# D1MBLUE.net
KiCad netlist of a schematic drawn in EAGLE
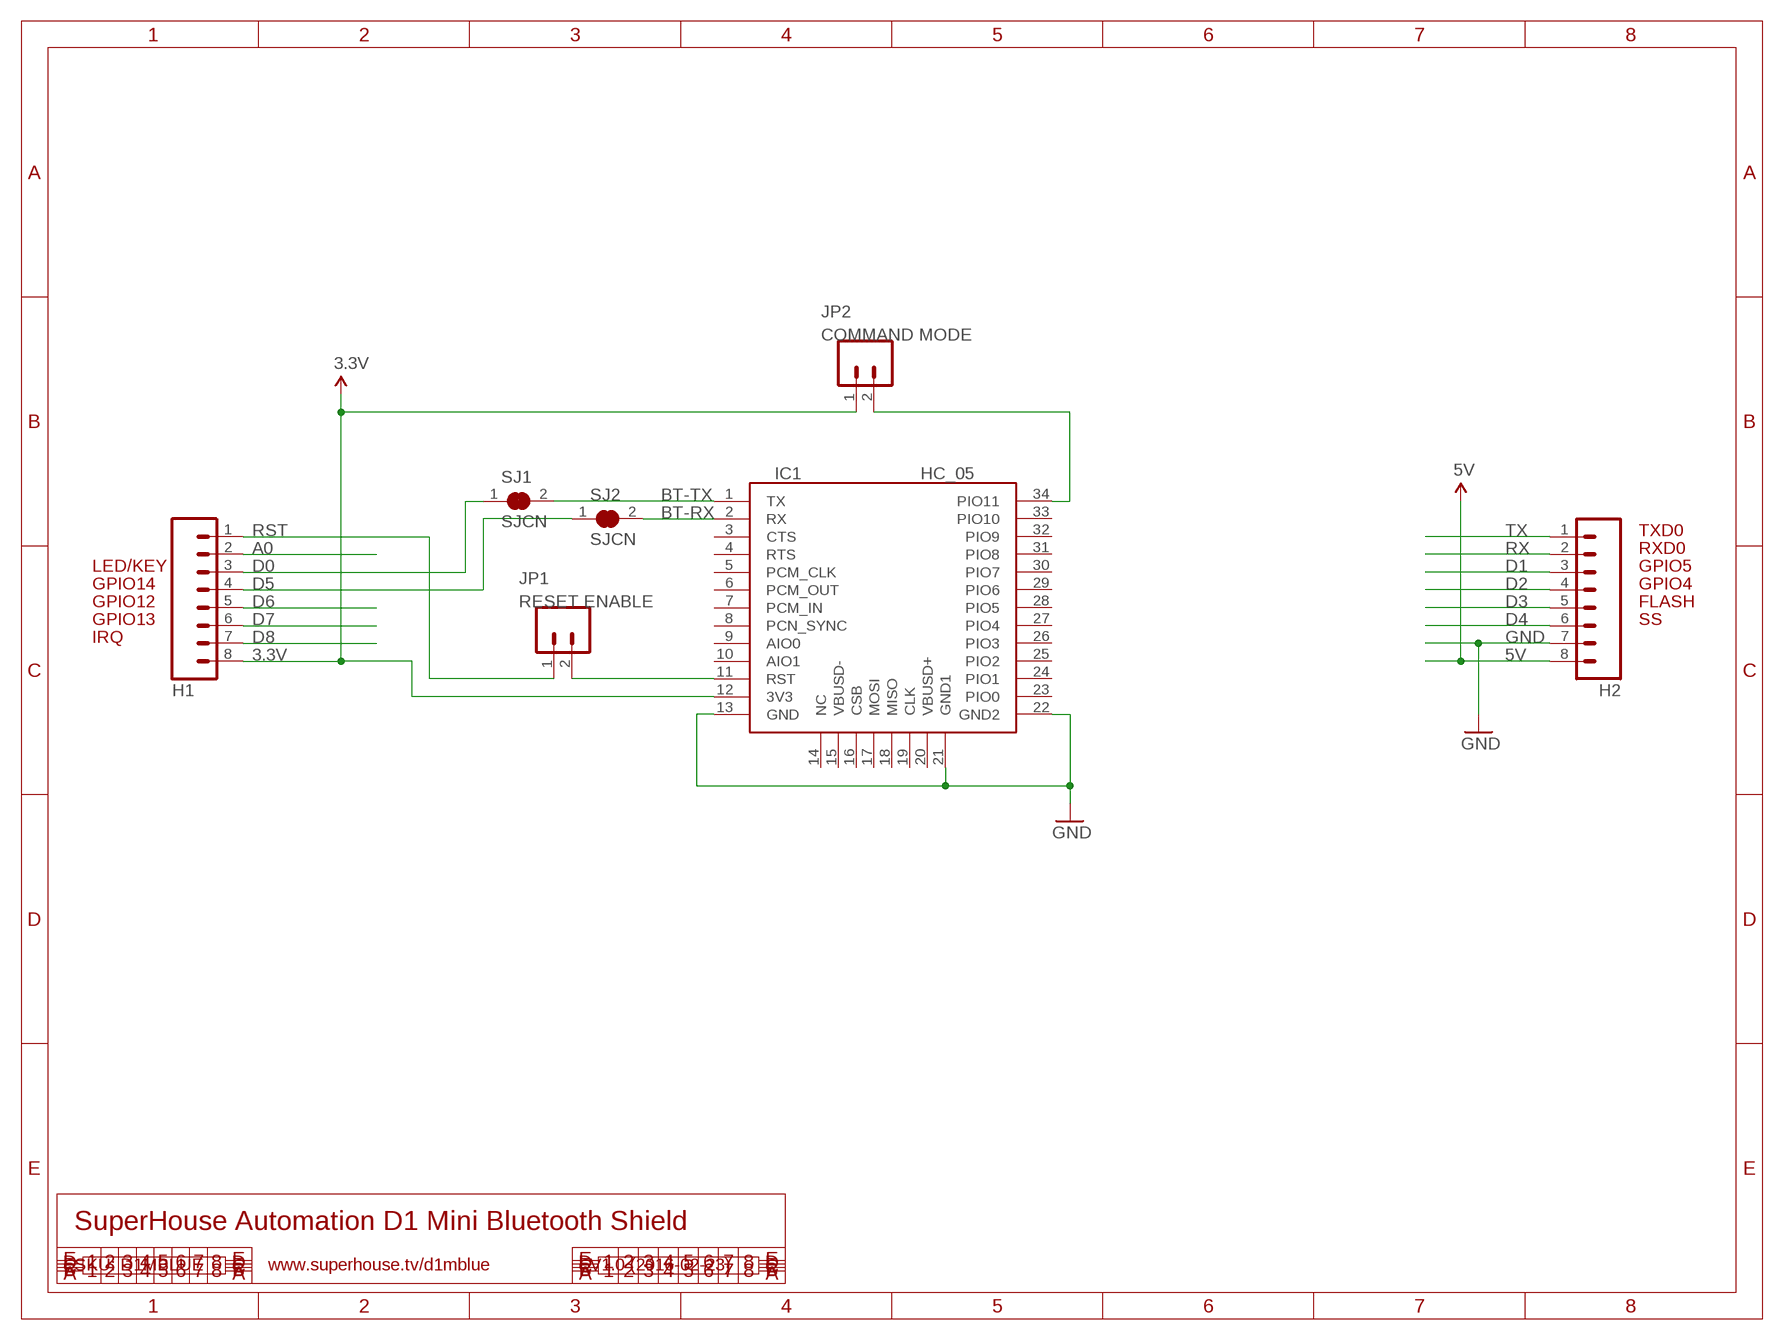
[diagram p0: schematic, sheet 1]

(export (version "E")
  (design (tool "Eeschema 10.0.6"))
  (components
    (comp (ref "H1")
      (value "M08")
      (footprint "eagle-import:1X08")
      (libsource (lib "eagle-import") (part "M08"))
    )
    (comp (ref "H2")
      (value "M08")
      (footprint "eagle-import:1X08")
      (libsource (lib "eagle-import") (part "M08"))
    )
    (comp (ref "IC1")
      (value "HC_05")
      (footprint "eagle-import:BLUETOOTH_SMD")
      (libsource (lib "eagle-import") (part "HC_05"))
    )
    (comp (ref "JP1")
      (value "RESET ENABLE")
      (footprint "eagle-import:1X02")
      (libsource (lib "eagle-import") (part "M02PTH"))
    )
    (comp (ref "JP2")
      (value "COMMAND MODE")
      (footprint "eagle-import:1X02")
      (libsource (lib "eagle-import") (part "M02PTH"))
    )
    (comp (ref "SJ1")
      (value "SJCN")
      (footprint "eagle-import:SJC")
      (libsource (lib "eagle-import") (part "SJCN"))
    )
    (comp (ref "SJ2")
      (value "SJCN")
      (footprint "eagle-import:SJC")
      (libsource (lib "eagle-import") (part "SJCN"))
    )
  )
  (nets
    (net (code "1") (name "/A0") (class "Default")
      (node (ref "H1") (pin "2") (pinfunction "2_2") (pintype "passive"))
    )
    (net (code "2") (name "/BT-RX") (class "Default")
      (node (ref "IC1") (pin "2") (pinfunction "RX_2") (pintype "bidirectional"))
      (node (ref "SJ2") (pin "2") (pinfunction "2_2") (pintype "passive"))
    )
    (net (code "3") (name "/BT-TX") (class "Default")
      (node (ref "IC1") (pin "1") (pinfunction "TX_1") (pintype "bidirectional"))
      (node (ref "SJ1") (pin "2") (pinfunction "2_2") (pintype "passive"))
    )
    (net (code "4") (name "/D0") (class "Default")
      (node (ref "H1") (pin "3") (pinfunction "3_3") (pintype "passive"))
      (node (ref "SJ1") (pin "1") (pinfunction "1_1") (pintype "passive"))
    )
    (net (code "5") (name "/D1") (class "Default")
      (node (ref "H2") (pin "3") (pinfunction "3_3") (pintype "passive"))
    )
    (net (code "6") (name "/D2") (class "Default")
      (node (ref "H2") (pin "4") (pinfunction "4_4") (pintype "passive"))
    )
    (net (code "7") (name "/D3") (class "Default")
      (node (ref "H2") (pin "5") (pinfunction "5_5") (pintype "passive"))
    )
    (net (code "8") (name "/D4") (class "Default")
      (node (ref "H2") (pin "6") (pinfunction "6_6") (pintype "passive"))
    )
    (net (code "9") (name "/D5") (class "Default")
      (node (ref "H1") (pin "4") (pinfunction "4_4") (pintype "passive"))
      (node (ref "SJ2") (pin "1") (pinfunction "1_1") (pintype "passive"))
    )
    (net (code "10") (name "/D6") (class "Default")
      (node (ref "H1") (pin "5") (pinfunction "5_5") (pintype "passive"))
    )
    (net (code "11") (name "/D7") (class "Default")
      (node (ref "H1") (pin "6") (pinfunction "6_6") (pintype "passive"))
    )
    (net (code "12") (name "/D8") (class "Default")
      (node (ref "H1") (pin "7") (pinfunction "7_7") (pintype "passive"))
    )
    (net (code "13") (name "/RST") (class "Default")
      (node (ref "H1") (pin "1") (pinfunction "1_1") (pintype "passive"))
      (node (ref "JP1") (pin "1") (pinfunction "1_1") (pintype "passive"))
    )
    (net (code "14") (name "/RX") (class "Default")
      (node (ref "H2") (pin "2") (pinfunction "2_2") (pintype "passive"))
    )
    (net (code "15") (name "/TX") (class "Default")
      (node (ref "H2") (pin "1") (pinfunction "1_1") (pintype "passive"))
    )
    (net (code "16") (name "3.3V") (class "Default")
      (node (ref "H1") (pin "8") (pinfunction "8_8") (pintype "passive"))
      (node (ref "IC1") (pin "12") (pinfunction "3V3_12") (pintype "bidirectional"))
      (node (ref "JP2") (pin "1") (pinfunction "1_1") (pintype "passive"))
    )
    (net (code "17") (name "5V") (class "Default")
      (node (ref "H2") (pin "8") (pinfunction "8_8") (pintype "passive"))
    )
    (net (code "18") (name "GND") (class "Default")
      (node (ref "H2") (pin "7") (pinfunction "7_7") (pintype "passive"))
      (node (ref "IC1") (pin "13") (pinfunction "GND_13") (pintype "bidirectional"))
      (node (ref "IC1") (pin "21") (pinfunction "GND1_21") (pintype "bidirectional"))
      (node (ref "IC1") (pin "22") (pinfunction "GND2_22") (pintype "bidirectional"))
    )
    (net (code "19") (name "Net-(IC1-PIO11)") (class "Default")
      (node (ref "IC1") (pin "34") (pinfunction "PIO11_34") (pintype "bidirectional"))
      (node (ref "JP2") (pin "2") (pinfunction "2_2") (pintype "passive"))
    )
    (net (code "20") (name "Net-(IC1-RST)") (class "Default")
      (node (ref "IC1") (pin "11") (pinfunction "RST_11") (pintype "bidirectional"))
      (node (ref "JP1") (pin "2") (pinfunction "2_2") (pintype "passive"))
    )
    (net (code "21") (name "unconnected-(IC1-AIO0-Pad9)") (class "Default")
      (node (ref "IC1") (pin "9") (pinfunction "AIO0_9") (pintype "bidirectional"))
    )
    (net (code "22") (name "unconnected-(IC1-AIO1-Pad10)") (class "Default")
      (node (ref "IC1") (pin "10") (pinfunction "AIO1_10") (pintype "bidirectional"))
    )
    (net (code "23") (name "unconnected-(IC1-CLK-Pad19)") (class "Default")
      (node (ref "IC1") (pin "19") (pinfunction "CLK_19") (pintype "bidirectional"))
    )
    (net (code "24") (name "unconnected-(IC1-CSB-Pad16)") (class "Default")
      (node (ref "IC1") (pin "16") (pinfunction "CSB_16") (pintype "bidirectional"))
    )
    (net (code "25") (name "unconnected-(IC1-CTS-Pad3)") (class "Default")
      (node (ref "IC1") (pin "3") (pinfunction "CTS_3") (pintype "bidirectional"))
    )
    (net (code "26") (name "unconnected-(IC1-MISO-Pad18)") (class "Default")
      (node (ref "IC1") (pin "18") (pinfunction "MISO_18") (pintype "bidirectional"))
    )
    (net (code "27") (name "unconnected-(IC1-MOSI-Pad17)") (class "Default")
      (node (ref "IC1") (pin "17") (pinfunction "MOSI_17") (pintype "bidirectional"))
    )
    (net (code "28") (name "unconnected-(IC1-NC-Pad14)") (class "Default")
      (node (ref "IC1") (pin "14") (pinfunction "NC_14") (pintype "bidirectional"))
    )
    (net (code "29") (name "unconnected-(IC1-PCM_CLK-Pad5)") (class "Default")
      (node (ref "IC1") (pin "5") (pinfunction "PCM_CLK_5") (pintype "bidirectional"))
    )
    (net (code "30") (name "unconnected-(IC1-PCM_IN-Pad7)") (class "Default")
      (node (ref "IC1") (pin "7") (pinfunction "PCM_IN_7") (pintype "bidirectional"))
    )
    (net (code "31") (name "unconnected-(IC1-PCM_OUT-Pad6)") (class "Default")
      (node (ref "IC1") (pin "6") (pinfunction "PCM_OUT_6") (pintype "bidirectional"))
    )
    (net (code "32") (name "unconnected-(IC1-PCN_SYNC-Pad8)") (class "Default")
      (node (ref "IC1") (pin "8") (pinfunction "PCN_SYNC_8") (pintype "bidirectional"))
    )
    (net (code "33") (name "unconnected-(IC1-PIO0-Pad23)") (class "Default")
      (node (ref "IC1") (pin "23") (pinfunction "PIO0_23") (pintype "bidirectional"))
    )
    (net (code "34") (name "unconnected-(IC1-PIO1-Pad24)") (class "Default")
      (node (ref "IC1") (pin "24") (pinfunction "PIO1_24") (pintype "bidirectional"))
    )
    (net (code "35") (name "unconnected-(IC1-PIO2-Pad25)") (class "Default")
      (node (ref "IC1") (pin "25") (pinfunction "PIO2_25") (pintype "bidirectional"))
    )
    (net (code "36") (name "unconnected-(IC1-PIO3-Pad26)") (class "Default")
      (node (ref "IC1") (pin "26") (pinfunction "PIO3_26") (pintype "bidirectional"))
    )
    (net (code "37") (name "unconnected-(IC1-PIO4-Pad27)") (class "Default")
      (node (ref "IC1") (pin "27") (pinfunction "PIO4_27") (pintype "bidirectional"))
    )
    (net (code "38") (name "unconnected-(IC1-PIO5-Pad28)") (class "Default")
      (node (ref "IC1") (pin "28") (pinfunction "PIO5_28") (pintype "bidirectional"))
    )
    (net (code "39") (name "unconnected-(IC1-PIO6-Pad29)") (class "Default")
      (node (ref "IC1") (pin "29") (pinfunction "PIO6_29") (pintype "bidirectional"))
    )
    (net (code "40") (name "unconnected-(IC1-PIO7-Pad30)") (class "Default")
      (node (ref "IC1") (pin "30") (pinfunction "PIO7_30") (pintype "bidirectional"))
    )
    (net (code "41") (name "unconnected-(IC1-PIO8-Pad31)") (class "Default")
      (node (ref "IC1") (pin "31") (pinfunction "PIO8_31") (pintype "bidirectional"))
    )
    (net (code "42") (name "unconnected-(IC1-PIO9-Pad32)") (class "Default")
      (node (ref "IC1") (pin "32") (pinfunction "PIO9_32") (pintype "bidirectional"))
    )
    (net (code "43") (name "unconnected-(IC1-PIO10-Pad33)") (class "Default")
      (node (ref "IC1") (pin "33") (pinfunction "PIO10_33") (pintype "bidirectional"))
    )
    (net (code "44") (name "unconnected-(IC1-RTS-Pad4)") (class "Default")
      (node (ref "IC1") (pin "4") (pinfunction "RTS_4") (pintype "bidirectional"))
    )
    (net (code "45") (name "unconnected-(IC1-VBUSD+-Pad20)") (class "Default")
      (node (ref "IC1") (pin "20") (pinfunction "VBUSD+_20") (pintype "bidirectional"))
    )
    (net (code "46") (name "unconnected-(IC1-VBUSD--Pad15)") (class "Default")
      (node (ref "IC1") (pin "15") (pinfunction "VBUSD-_15") (pintype "bidirectional"))
    )
  )
)
